# MB1246.net
KiCad netlist of a schematic drawn in Altium Designer
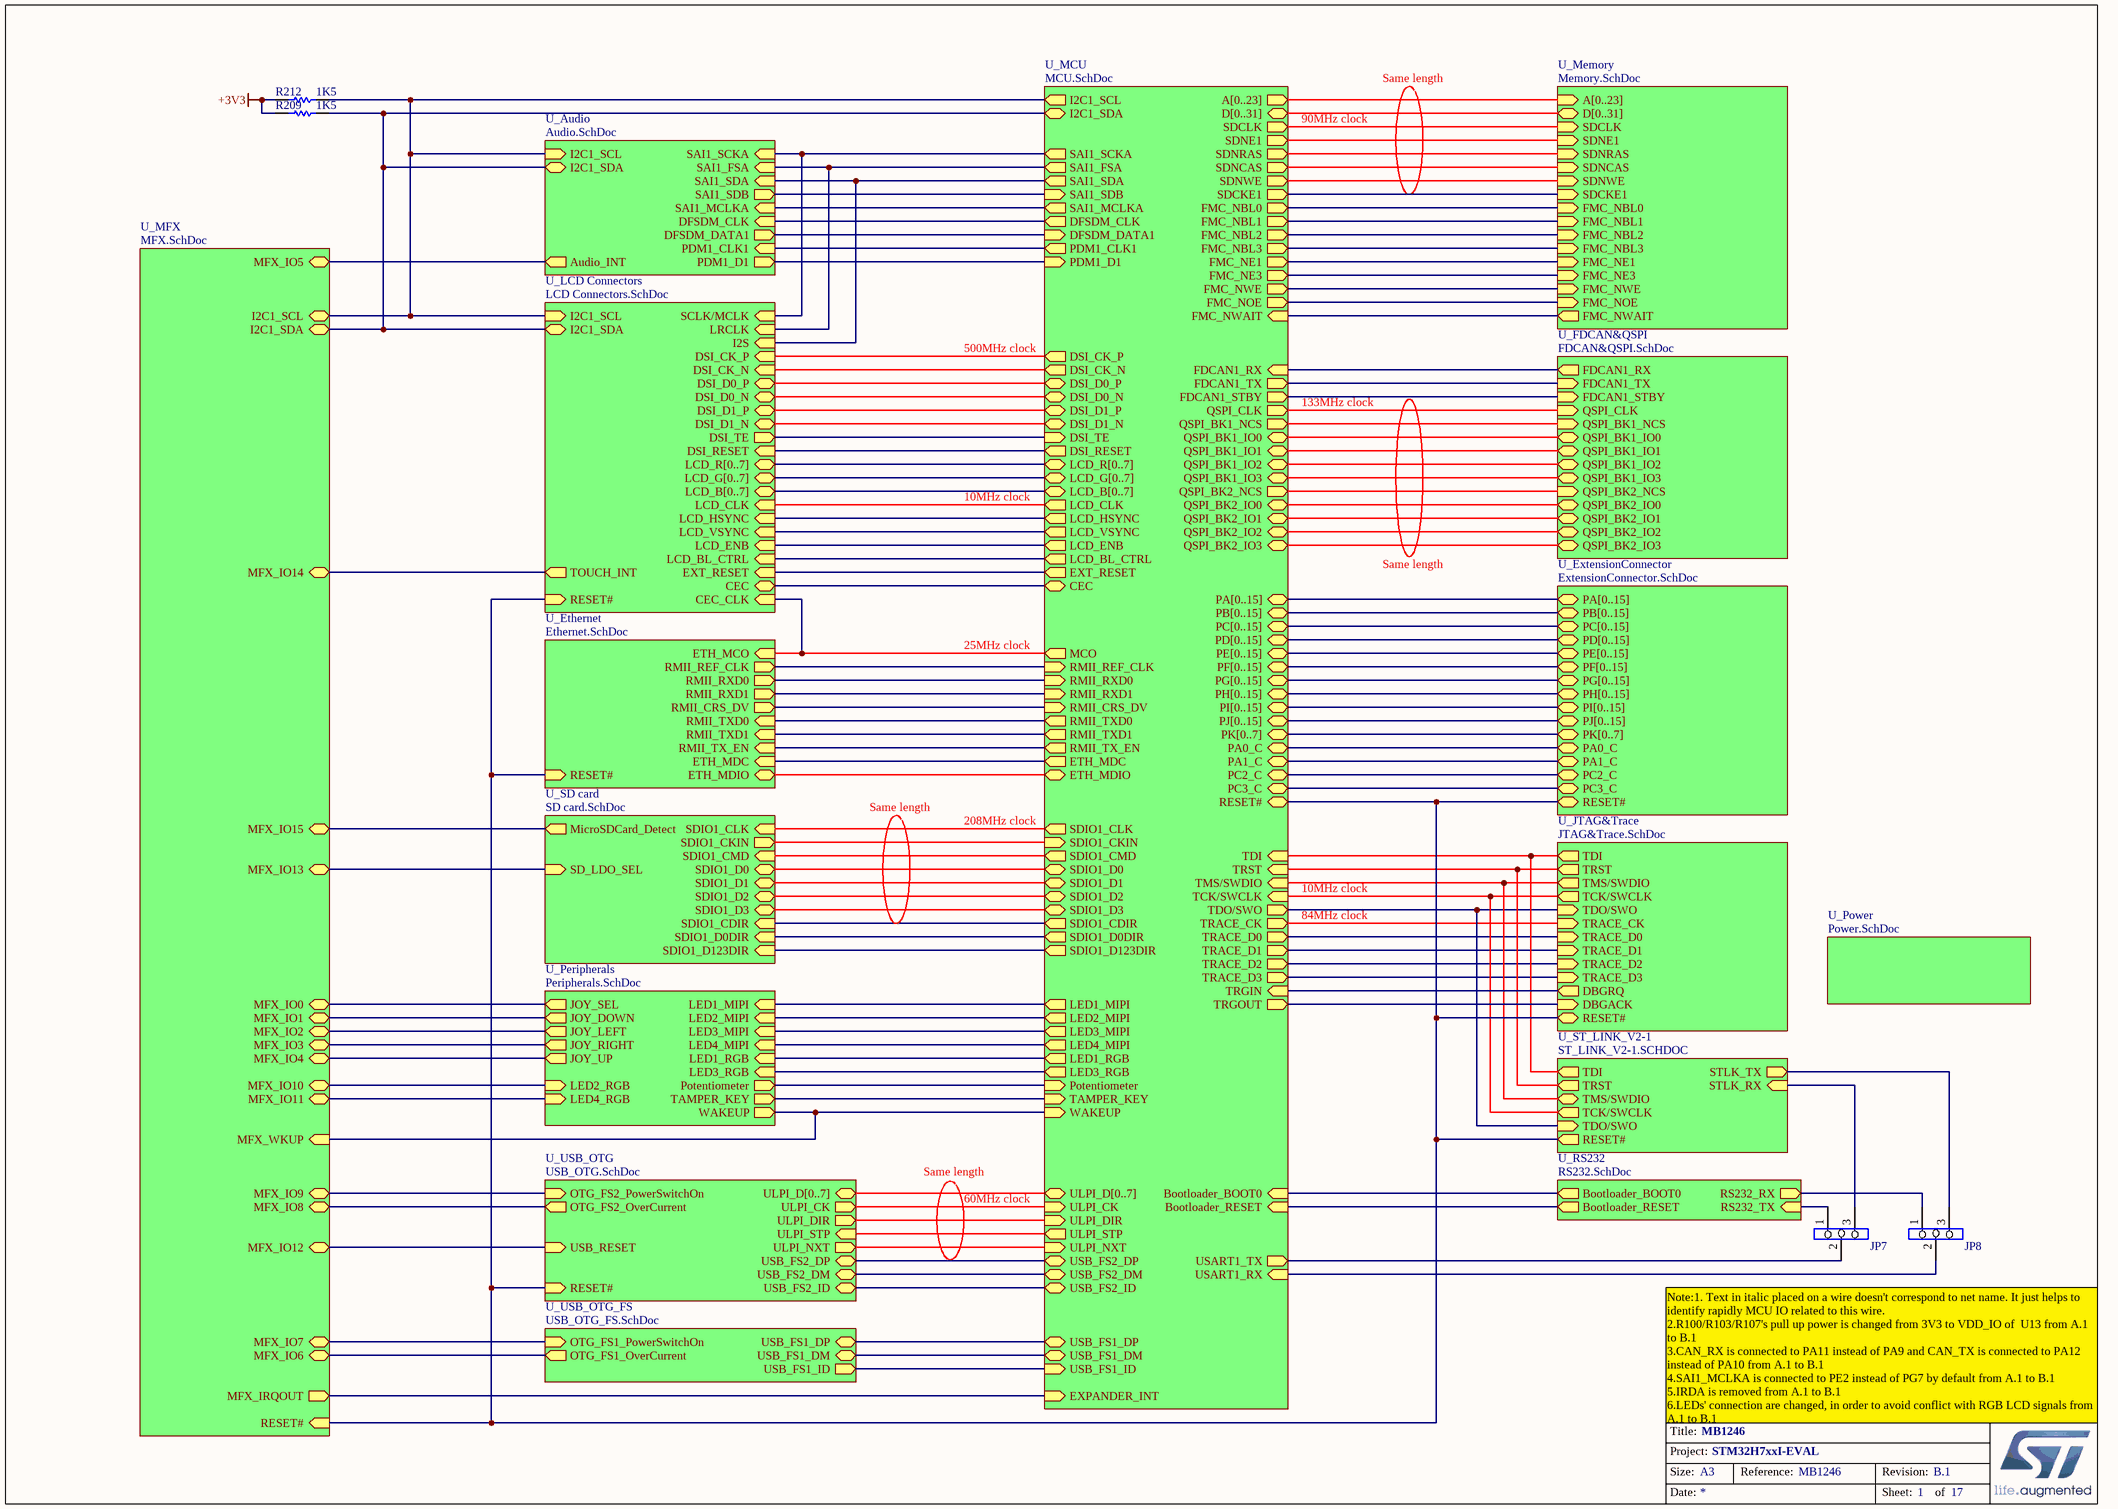
[diagram p0: MB1246.SchDoc]

(export (version "E")
  (design (tool "Eeschema 10.0.6"))
  (components
    (comp (ref "JP7") (value "~") (footprint "SIP3") (libsource (lib "STR910_SCHLIB") (part "Jumper3")))
    (comp (ref "JP8") (value "~") (footprint "SIP3") (libsource (lib "STR910_SCHLIB") (part "Jumper3")))
    (comp (ref "R209")
      (value "1K5")
      (footprint "0603R")
      (description "Resistor")
      (fields (field (name "PUBLISHER") "Altium Limited"))
      (libsource (lib "Miscellaneous Devices") (part "Res1"))
    )
    (comp (ref "R212")
      (value "1K5")
      (footprint "0603R")
      (description "Resistor")
      (fields (field (name "PUBLISHER") "Altium Limited"))
      (libsource (lib "Miscellaneous Devices") (part "Res1"))
    )
  )
  (nets
    (net (code "1") (name "+3V3") (class "Default")
      (node (ref "R209") (pin "1") (pinfunction "1_1") (pintype "passive"))
      (node (ref "R212") (pin "1") (pinfunction "1_1") (pintype "passive"))
    )
    (net (code "34") (name "/I2C1_SCL") (class "Default")
      (node (ref "R212") (pin "2") (pinfunction "2_2") (pintype "passive"))
    )
    (net (code "35") (name "/I2C1_SDA") (class "Default")
      (node (ref "R209") (pin "2") (pinfunction "2_2") (pintype "passive"))
    )
    (net (code "103") (name "/RS232_RX") (class "Default") (node (ref "JP8") (pin "1") (pintype "passive")))
    (net (code "104") (name "/RS232_TX") (class "Default") (node (ref "JP7") (pin "1") (pintype "passive")))
    (net (code "126") (name "/STLK_RX") (class "Default") (node (ref "JP7") (pin "3") (pintype "passive")))
    (net (code "127") (name "/STLK_TX") (class "Default") (node (ref "JP8") (pin "3") (pintype "passive")))
    (net (code "146") (name "/USART1_RX") (class "Default") (node (ref "JP8") (pin "2") (pintype "passive")))
    (net (code "147") (name "/USART1_TX") (class "Default") (node (ref "JP7") (pin "2") (pintype "passive")))
  )
)
